# inmux.net
KiCad netlist of a schematic drawn in Altium Designer
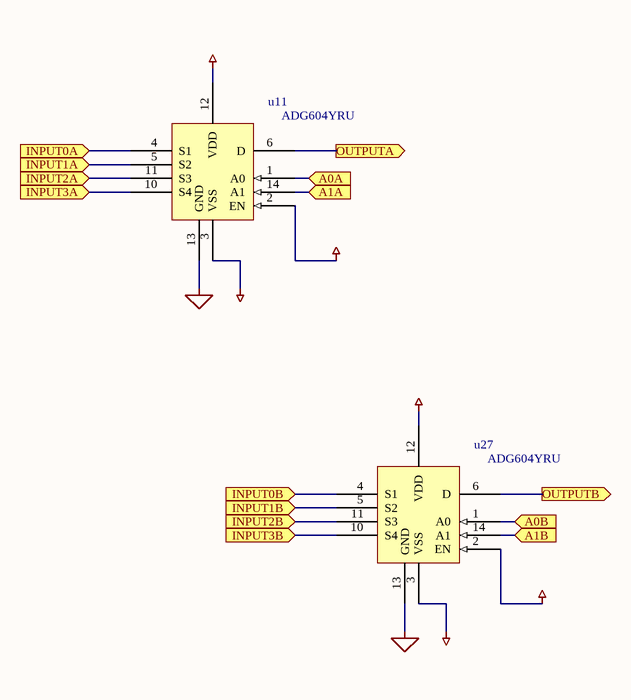
[diagram p0: inmux.SCHDOC]

(export (version "E")
  (design (tool "Eeschema 10.0.6"))
  (components
    (comp (ref "u11")
      (value "ADG604YRU")
      (footprint "SSO-G14/X.4")
      (description "1 pC Charge Injection 100pA leakage CMOS 4-channel mux")
      (libsource (lib "parts") (part "ADG604"))
    )
    (comp (ref "u27")
      (value "ADG604YRU")
      (footprint "SSO-G14/X.4")
      (description "1 pC Charge Injection 100pA leakage CMOS 4-channel mux")
      (libsource (lib "parts") (part "ADG604"))
    )
  )
  (nets
    (net (code "1") (name "/A0A") (class "Default")
      (node (ref "u11") (pin "1") (pinfunction "A0_1") (pintype "input"))
    )
    (net (code "2") (name "/A0B") (class "Default")
      (node (ref "u27") (pin "1") (pinfunction "A0_1") (pintype "input"))
    )
    (net (code "3") (name "/A1A") (class "Default")
      (node (ref "u11") (pin "14") (pinfunction "A1_14") (pintype "input"))
    )
    (net (code "4") (name "/A1B") (class "Default")
      (node (ref "u27") (pin "14") (pinfunction "A1_14") (pintype "input"))
    )
    (net (code "5") (name "/INPUT0A") (class "Default")
      (node (ref "u11") (pin "4") (pinfunction "S1_4") (pintype "passive"))
    )
    (net (code "6") (name "/INPUT0B") (class "Default")
      (node (ref "u27") (pin "4") (pinfunction "S1_4") (pintype "passive"))
    )
    (net (code "7") (name "/INPUT1A") (class "Default")
      (node (ref "u11") (pin "5") (pinfunction "S2_5") (pintype "passive"))
    )
    (net (code "8") (name "/INPUT1B") (class "Default")
      (node (ref "u27") (pin "5") (pinfunction "S2_5") (pintype "passive"))
    )
    (net (code "9") (name "/INPUT2A") (class "Default")
      (node (ref "u11") (pin "11") (pinfunction "S3_11") (pintype "passive"))
    )
    (net (code "10") (name "/INPUT2B") (class "Default")
      (node (ref "u27") (pin "11") (pinfunction "S3_11") (pintype "passive"))
    )
    (net (code "11") (name "/INPUT3A") (class "Default")
      (node (ref "u11") (pin "10") (pinfunction "S4_10") (pintype "passive"))
    )
    (net (code "12") (name "/INPUT3B") (class "Default")
      (node (ref "u27") (pin "10") (pinfunction "S4_10") (pintype "passive"))
    )
    (net (code "13") (name "/OUTPUTA") (class "Default")
      (node (ref "u11") (pin "6") (pinfunction "D_6") (pintype "passive"))
    )
    (net (code "14") (name "/OUTPUTB") (class "Default")
      (node (ref "u27") (pin "6") (pinfunction "D_6") (pintype "passive"))
    )
    (net (code "15") (name "AGND") (class "Default")
      (node (ref "u11") (pin "13") (pinfunction "GND_13") (pintype "power_in"))
      (node (ref "u27") (pin "13") (pinfunction "GND_13") (pintype "power_in"))
    )
    (net (code "16") (name "AVDD") (class "Default")
      (node (ref "u11") (pin "12") (pinfunction "VDD_12") (pintype "power_in"))
      (node (ref "u11") (pin "2") (pinfunction "EN_2") (pintype "input"))
      (node (ref "u27") (pin "12") (pinfunction "VDD_12") (pintype "power_in"))
      (node (ref "u27") (pin "2") (pinfunction "EN_2") (pintype "input"))
    )
    (net (code "17") (name "AVSS") (class "Default")
      (node (ref "u11") (pin "3") (pinfunction "VSS_3") (pintype "power_in"))
      (node (ref "u27") (pin "3") (pinfunction "VSS_3") (pintype "power_in"))
    )
  )
)
